# 32B48P_Dev_Board.net
KiCad netlist of a schematic drawn in Altium Designer
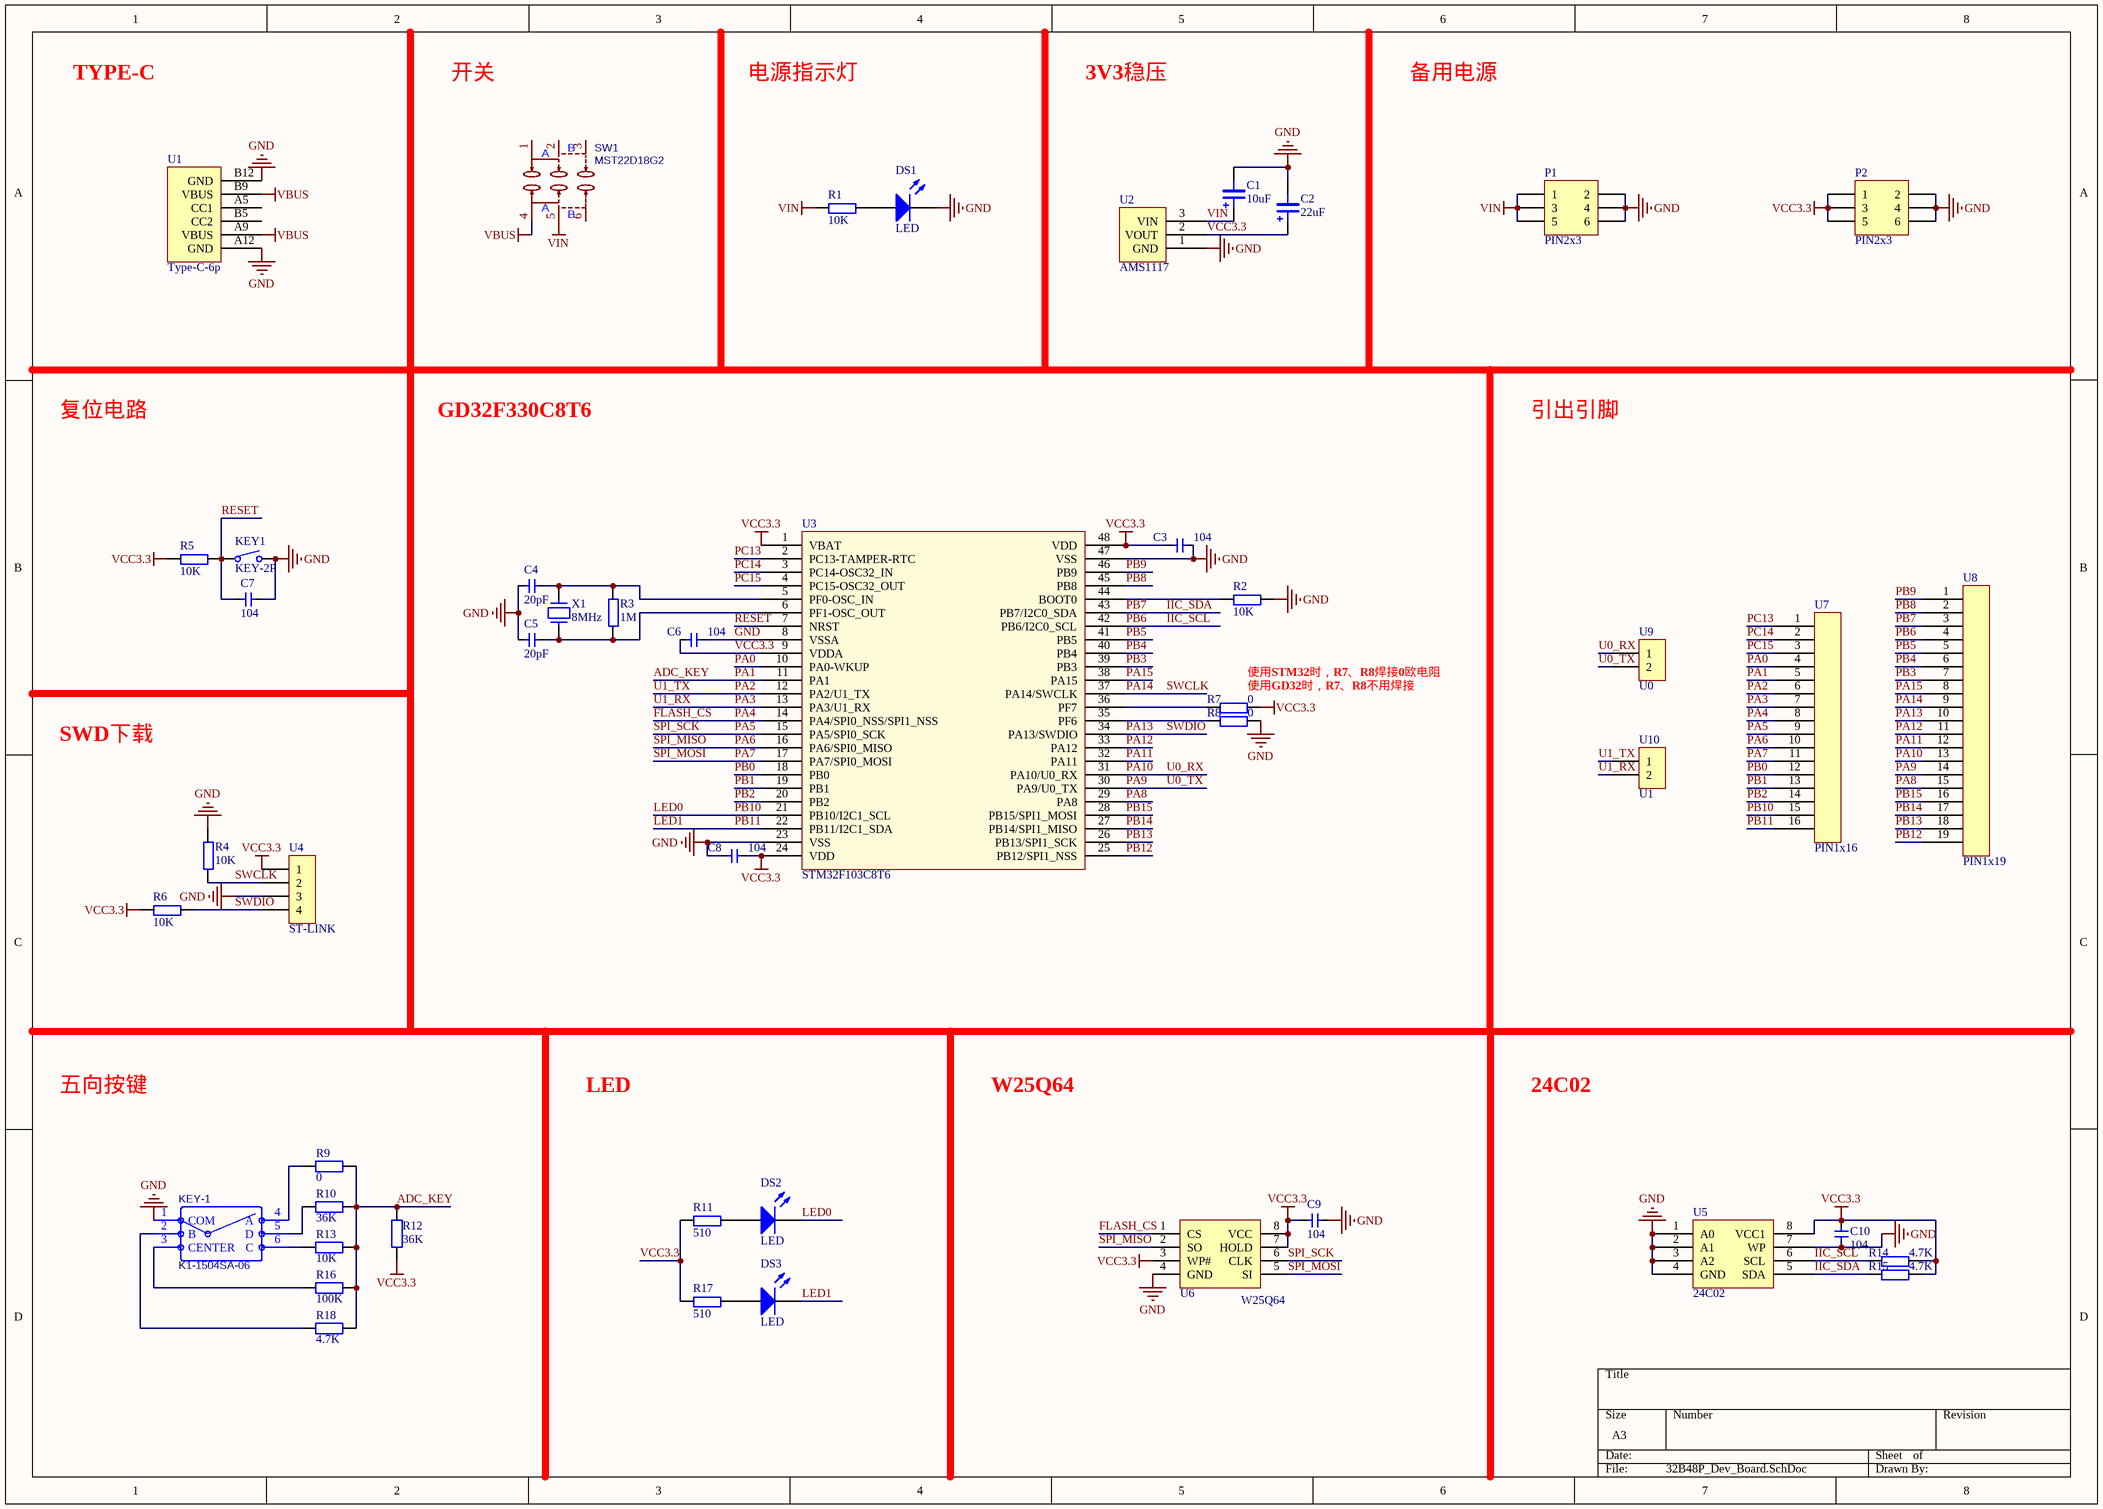
[diagram p0: 32B48P_Dev_Board.SchDoc]

(export (version "E")
  (design (tool "Eeschema 10.0.6"))
  (components
    (comp (ref "C1")
      (value "10uF")
      (footprint "CAP-TANTALUM-A")
      (description "Tantalum Capacitor")
      (libsource (lib "altium-import") (part "root_1_CAP-TANTALUM_"))
    )
    (comp (ref "C2")
      (value "22uF")
      (footprint "CAP-TANTALUM-A")
      (description "Tantalum Capacitor")
      (libsource (lib "altium-import") (part "root_1_CAP-TANTALUM_"))
    )
    (comp (ref "C3")
      (value "104")
      (footprint "Cap_0603")
      (description "Capacitor")
      (libsource (lib "altium-import") (part "root_0_CAP_"))
    )
    (comp (ref "C4")
      (value "20pF")
      (footprint "Cap_0603")
      (description "Capacitor")
      (libsource (lib "altium-import") (part "root_0_CAP_"))
    )
    (comp (ref "C5")
      (value "20pF")
      (footprint "Cap_0603")
      (description "Capacitor")
      (libsource (lib "altium-import") (part "root_0_CAP_"))
    )
    (comp (ref "C6")
      (value "104")
      (footprint "Cap_0603")
      (description "Capacitor")
      (libsource (lib "altium-import") (part "root_0_CAP_"))
    )
    (comp (ref "C7")
      (value "104")
      (footprint "Cap_0603")
      (description "Capacitor")
      (libsource (lib "altium-import") (part "root_0_CAP_"))
    )
    (comp (ref "C8")
      (value "104")
      (footprint "Cap_0603")
      (description "Capacitor")
      (libsource (lib "altium-import") (part "root_0_CAP_"))
    )
    (comp (ref "C9")
      (value "104")
      (footprint "Cap_0603")
      (description "Capacitor")
      (libsource (lib "altium-import") (part "root_0_CAP_"))
    )
    (comp (ref "C10")
      (value "104")
      (footprint "Cap_0603")
      (description "Capacitor")
      (libsource (lib "altium-import") (part "root_1_CAP_"))
    )
    (comp (ref "DS1")
      (value "LED")
      (footprint "LED_0603")
      (fields (field (name "PUBLISHER") "Altium Limited"))
      (libsource (lib "altium-import") (part "root_0_LED_"))
    )
    (comp (ref "DS2")
      (value "LED")
      (footprint "LED_0603")
      (fields (field (name "PUBLISHER") "Altium Limited"))
      (libsource (lib "altium-import") (part "root_0_LED_"))
    )
    (comp (ref "DS3")
      (value "LED")
      (footprint "LED_0603")
      (fields (field (name "PUBLISHER") "Altium Limited"))
      (libsource (lib "altium-import") (part "root_0_LED_"))
    )
    (comp (ref "KEY-1")
      (value "K1-1504SA-06")
      (footprint "SW-SMD_K1-1504SA-06")
      (description "五向按键")
      (fields (field (name "BOM_SUPPLIER PART") "C136712") (field (name "CONTRIBUTOR") "LCSC"))
      (libsource (lib "altium-import") (part "root_0_K1-1504SA-06_"))
    )
    (comp (ref "KEY1")
      (value "KEY-2P")
      (footprint "key3*6")
      (description "Switch")
      (libsource (lib "altium-import") (part "root_0_KEY-2P_"))
    )
    (comp (ref "P1")
      (value "PIN2x3")
      (footprint "PIN-2x3-2.54-1.0")
      (description "Connector")
      (libsource (lib "altium-import") (part "root_0_PIN2x3_"))
    )
    (comp (ref "P2")
      (value "PIN2x3")
      (footprint "PIN-2x3-2.54-1.0")
      (description "Connector")
      (libsource (lib "altium-import") (part "root_0_PIN2x3_"))
    )
    (comp (ref "R1")
      (value "10K")
      (footprint "Res_0603")
      (libsource (lib "altium-import") (part "root_0_RES_"))
    )
    (comp (ref "R2")
      (value "10K")
      (footprint "Res_0603")
      (libsource (lib "altium-import") (part "root_0_RES_"))
    )
    (comp (ref "R3")
      (value "1M")
      (footprint "Res_0603")
      (libsource (lib "altium-import") (part "root_1_RES_"))
    )
    (comp (ref "R4")
      (value "10K")
      (footprint "Res_0603")
      (libsource (lib "altium-import") (part "root_1_RES_"))
    )
    (comp (ref "R5")
      (value "10K")
      (footprint "Res_0603")
      (libsource (lib "altium-import") (part "root_0_RES_"))
    )
    (comp (ref "R6")
      (value "10K")
      (footprint "Res_0603")
      (libsource (lib "altium-import") (part "root_0_RES_"))
    )
    (comp (ref "R7")
      (value "0")
      (footprint "Res_0603")
      (libsource (lib "altium-import") (part "root_0_RES_"))
    )
    (comp (ref "R8")
      (value "0")
      (footprint "Res_0603")
      (libsource (lib "altium-import") (part "root_0_RES_"))
    )
    (comp (ref "R9")
      (value "0")
      (footprint "Res_0603")
      (description "Resistor")
      (libsource (lib "") (part "root_0_RES__1"))
    )
    (comp (ref "R10")
      (value "36K")
      (footprint "Res_0603")
      (description "Resistor")
      (libsource (lib "") (part "root_0_RES__1"))
    )
    (comp (ref "R11")
      (value "510")
      (footprint "Res_0603")
      (libsource (lib "altium-import") (part "root_0_RES_"))
    )
    (comp (ref "R12")
      (value "36K")
      (footprint "Res_0603")
      (description "Resistor")
      (libsource (lib "") (part "root_1_RES__1"))
    )
    (comp (ref "R13")
      (value "10K")
      (footprint "Res_0603")
      (description "Resistor")
      (libsource (lib "") (part "root_0_RES__1"))
    )
    (comp (ref "R14")
      (value "4.7K")
      (footprint "Res_0603")
      (libsource (lib "altium-import") (part "root_0_RES_"))
    )
    (comp (ref "R15")
      (value "4.7K")
      (footprint "Res_0603")
      (libsource (lib "altium-import") (part "root_0_RES_"))
    )
    (comp (ref "R16")
      (value "100K")
      (footprint "Res_0603")
      (description "Resistor")
      (libsource (lib "") (part "root_0_RES__1"))
    )
    (comp (ref "R17")
      (value "510")
      (footprint "Res_0603")
      (libsource (lib "altium-import") (part "root_0_RES_"))
    )
    (comp (ref "R18")
      (value "4.7K")
      (footprint "Res_0603")
      (description "Resistor")
      (libsource (lib "") (part "root_0_RES__1"))
    )
    (comp (ref "SW1")
      (value "MST22D18G2")
      (footprint "6脚拨动开关")
      (fields (field (name "BOM_SUPPLIER PART") "C431544") (field (name "CONTRIBUTOR") "LCSC"))
      (libsource (lib "altium-import") (part "root_0_6脚拨动开关_"))
    )
    (comp (ref "U1")
      (value "Type-C-6p")
      (footprint "TYPEC-6P")
      (libsource (lib "altium-import") (part "root_0_Type-C-6p_"))
    )
    (comp (ref "U2")
      (value "AMS1117")
      (footprint "SOT-89")
      (libsource (lib "altium-import") (part "root_2_AMS1117_"))
    )
    (comp (ref "U3")
      (value "STM32F103C8T6")
      (footprint "QFP-48-0.5")
      (libsource (lib "altium-import") (part "root_0_GD32F330Cx_"))
    )
    (comp (ref "U4")
      (value "ST-LINK")
      (footprint "st-link")
      (description "Connector")
      (libsource (lib "altium-import") (part "root_0_PIN1x4_"))
    )
    (comp (ref "U5")
      (value "24C02")
      (footprint "SOIC-8")
      (libsource (lib "altium-import") (part "root_0_24C02_"))
    )
    (comp (ref "U6")
      (value "W25Q64")
      (footprint "SOIC-8")
      (libsource (lib "altium-import") (part "root_0_W25Q64_"))
    )
    (comp (ref "U7")
      (value "PIN1x16")
      (footprint "PIN1x16")
      (libsource (lib "altium-import") (part "root_0_PIN1x16_"))
    )
    (comp (ref "U8")
      (value "PIN1x19")
      (footprint "PIN1x19")
      (libsource (lib "altium-import") (part "root_0_PIN1x19_"))
    )
    (comp (ref "U9")
      (value "U0")
      (footprint "PIN-1x2-2.54")
      (description "Connector")
      (libsource (lib "altium-import") (part "root_0_PIN1x2_"))
    )
    (comp (ref "U10")
      (value "U1")
      (footprint "PIN-1x2-2.54")
      (description "Connector")
      (libsource (lib "altium-import") (part "root_0_PIN1x2_"))
    )
    (comp (ref "X1")
      (value "8MHz")
      (footprint "OSC 5032-2P")
      (description "Crystal")
      (libsource (lib "altium-import") (part "root_0_Crystal_"))
    )
  )
  (nets
    (net (code "1") (name "/ADC_KEY") (class "Default")
      (node (ref "R10") (pin "2") (pinfunction "2_2") (pintype "passive"))
      (node (ref "R12") (pin "2") (pinfunction "2_2") (pintype "passive"))
      (node (ref "R13") (pin "2") (pinfunction "2_2") (pintype "passive"))
      (node (ref "R16") (pin "2") (pinfunction "2_2") (pintype "passive"))
      (node (ref "R18") (pin "2") (pinfunction "2_2") (pintype "passive"))
      (node (ref "R9") (pin "2") (pinfunction "2_2") (pintype "passive"))
      (node (ref "U3") (pin "11") (pinfunction "PA1_11") (pintype "passive"))
      (node (ref "U7") (pin "5") (pinfunction "5_5") (pintype "passive"))
    )
    (net (code "2") (name "/FLASH_CS") (class "Default")
      (node (ref "U3") (pin "14") (pinfunction "PA4/SPI0_NSS/SPI1_NSS_14") (pintype "passive"))
      (node (ref "U6") (pin "1") (pinfunction "CS_1") (pintype "passive"))
      (node (ref "U7") (pin "8") (pinfunction "8_8") (pintype "passive"))
    )
    (net (code "3") (name "/IIC_SCL") (class "Default")
      (node (ref "R14") (pin "1") (pintype "passive"))
      (node (ref "U3") (pin "42") (pinfunction "PB6/I2C0_SCL_42") (pintype "passive"))
      (node (ref "U5") (pin "6") (pinfunction "SCL_6") (pintype "passive"))
      (node (ref "U8") (pin "4") (pinfunction "4_4") (pintype "passive"))
    )
    (net (code "4") (name "/IIC_SDA") (class "Default")
      (node (ref "R15") (pin "1") (pintype "passive"))
      (node (ref "U3") (pin "43") (pinfunction "PB7/I2C0_SDA_43") (pintype "passive"))
      (node (ref "U5") (pin "5") (pinfunction "SDA_5") (pintype "passive"))
      (node (ref "U8") (pin "3") (pinfunction "3_3") (pintype "passive"))
    )
    (net (code "5") (name "/LED0") (class "Default")
      (node (ref "DS2") (pin "2") (pinfunction "K_2") (pintype "passive"))
      (node (ref "U3") (pin "21") (pinfunction "PB10/I2C1_SCL_21") (pintype "passive"))
      (node (ref "U7") (pin "15") (pinfunction "15_15") (pintype "passive"))
    )
    (net (code "6") (name "/LED1") (class "Default")
      (node (ref "DS3") (pin "2") (pinfunction "K_2") (pintype "passive"))
      (node (ref "U3") (pin "22") (pinfunction "PB11/I2C1_SDA_22") (pintype "passive"))
      (node (ref "U7") (pin "16") (pinfunction "16_16") (pintype "passive"))
    )
    (net (code "7") (name "/PA0") (class "Default")
      (node (ref "U3") (pin "10") (pinfunction "PA0-WKUP_10") (pintype "passive"))
      (node (ref "U7") (pin "4") (pinfunction "4_4") (pintype "passive"))
    )
    (net (code "8") (name "/PA2") (class "Default")
      (node (ref "U10") (pin "1") (pinfunction "1_1") (pintype "passive"))
      (node (ref "U3") (pin "12") (pinfunction "PA2/U1_TX_12") (pintype "passive"))
      (node (ref "U7") (pin "6") (pinfunction "6_6") (pintype "passive"))
    )
    (net (code "9") (name "/PA3") (class "Default")
      (node (ref "U10") (pin "2") (pinfunction "2_2") (pintype "passive"))
      (node (ref "U3") (pin "13") (pinfunction "PA3/U1_RX_13") (pintype "passive"))
      (node (ref "U7") (pin "7") (pinfunction "7_7") (pintype "passive"))
    )
    (net (code "10") (name "/PA5") (class "Default")
      (node (ref "U3") (pin "15") (pinfunction "PA5/SPI0_SCK_15") (pintype "passive"))
      (node (ref "U6") (pin "6") (pinfunction "CLK_6") (pintype "passive"))
      (node (ref "U7") (pin "9") (pinfunction "9_9") (pintype "passive"))
    )
    (net (code "11") (name "/PA6") (class "Default")
      (node (ref "U3") (pin "16") (pinfunction "PA6/SPI0_MISO_16") (pintype "passive"))
      (node (ref "U6") (pin "2") (pinfunction "SO_2") (pintype "passive"))
      (node (ref "U7") (pin "10") (pinfunction "10_10") (pintype "passive"))
    )
    (net (code "12") (name "/PA7") (class "Default")
      (node (ref "U3") (pin "17") (pinfunction "PA7/SPI0_MOSI_17") (pintype "passive"))
      (node (ref "U6") (pin "5") (pinfunction "SI_5") (pintype "passive"))
      (node (ref "U7") (pin "11") (pinfunction "11_11") (pintype "passive"))
    )
    (net (code "13") (name "/PA8") (class "Default")
      (node (ref "U3") (pin "29") (pinfunction "PA8_29") (pintype "passive"))
      (node (ref "U8") (pin "15") (pinfunction "15_15") (pintype "passive"))
    )
    (net (code "14") (name "/PA9") (class "Default")
      (node (ref "U3") (pin "30") (pinfunction "PA9/U0_TX_30") (pintype "passive"))
      (node (ref "U8") (pin "14") (pinfunction "14_14") (pintype "passive"))
      (node (ref "U9") (pin "2") (pinfunction "2_2") (pintype "passive"))
    )
    (net (code "15") (name "/PA10") (class "Default")
      (node (ref "U3") (pin "31") (pinfunction "PA10/U0_RX_31") (pintype "passive"))
      (node (ref "U8") (pin "13") (pinfunction "13_13") (pintype "passive"))
      (node (ref "U9") (pin "1") (pinfunction "1_1") (pintype "passive"))
    )
    (net (code "16") (name "/PA11") (class "Default")
      (node (ref "U3") (pin "32") (pinfunction "PA11_32") (pintype "passive"))
      (node (ref "U8") (pin "12") (pinfunction "12_12") (pintype "passive"))
    )
    (net (code "17") (name "/PA12") (class "Default")
      (node (ref "U3") (pin "33") (pinfunction "PA12_33") (pintype "passive"))
      (node (ref "U8") (pin "11") (pinfunction "11_11") (pintype "passive"))
    )
    (net (code "18") (name "/PA13") (class "Default")
      (node (ref "R6") (pin "2") (pintype "passive"))
      (node (ref "U3") (pin "34") (pinfunction "PA13/SWDIO_34") (pintype "passive"))
      (node (ref "U4") (pin "4") (pinfunction "4_4") (pintype "passive"))
      (node (ref "U8") (pin "10") (pinfunction "10_10") (pintype "passive"))
    )
    (net (code "19") (name "/PA14") (class "Default")
      (node (ref "R4") (pin "1") (pintype "passive"))
      (node (ref "U3") (pin "37") (pinfunction "PA14/SWCLK_37") (pintype "passive"))
      (node (ref "U4") (pin "2") (pinfunction "2_2") (pintype "passive"))
      (node (ref "U8") (pin "9") (pinfunction "9_9") (pintype "passive"))
    )
    (net (code "20") (name "/PA15") (class "Default")
      (node (ref "U3") (pin "38") (pinfunction "PA15_38") (pintype "passive"))
      (node (ref "U8") (pin "8") (pinfunction "8_8") (pintype "passive"))
    )
    (net (code "21") (name "/PB0") (class "Default")
      (node (ref "U3") (pin "18") (pinfunction "PB0_18") (pintype "passive"))
      (node (ref "U7") (pin "12") (pinfunction "12_12") (pintype "passive"))
    )
    (net (code "22") (name "/PB1") (class "Default")
      (node (ref "U3") (pin "19") (pinfunction "PB1_19") (pintype "passive"))
      (node (ref "U7") (pin "13") (pinfunction "13_13") (pintype "passive"))
    )
    (net (code "23") (name "/PB2") (class "Default")
      (node (ref "U3") (pin "20") (pinfunction "PB2_20") (pintype "passive"))
      (node (ref "U7") (pin "14") (pinfunction "14_14") (pintype "passive"))
    )
    (net (code "24") (name "/PB3") (class "Default")
      (node (ref "U3") (pin "39") (pinfunction "PB3_39") (pintype "passive"))
      (node (ref "U8") (pin "7") (pinfunction "7_7") (pintype "passive"))
    )
    (net (code "25") (name "/PB4") (class "Default")
      (node (ref "U3") (pin "40") (pinfunction "PB4_40") (pintype "passive"))
      (node (ref "U8") (pin "6") (pinfunction "6_6") (pintype "passive"))
    )
    (net (code "26") (name "/PB5") (class "Default")
      (node (ref "U3") (pin "41") (pinfunction "PB5_41") (pintype "passive"))
      (node (ref "U8") (pin "5") (pinfunction "5_5") (pintype "passive"))
    )
    (net (code "27") (name "/PB8") (class "Default")
      (node (ref "U3") (pin "45") (pinfunction "PB8_45") (pintype "passive"))
      (node (ref "U8") (pin "2") (pinfunction "2_2") (pintype "passive"))
    )
    (net (code "28") (name "/PB9") (class "Default")
      (node (ref "U3") (pin "46") (pinfunction "PB9_46") (pintype "passive"))
      (node (ref "U8") (pin "1") (pinfunction "1_1") (pintype "passive"))
    )
    (net (code "29") (name "/PB12") (class "Default")
      (node (ref "U3") (pin "25") (pinfunction "PB12/SPI1_NSS_25") (pintype "passive"))
      (node (ref "U8") (pin "19") (pinfunction "19_19") (pintype "passive"))
    )
    (net (code "30") (name "/PB13") (class "Default")
      (node (ref "U3") (pin "26") (pinfunction "PB13/SPI1_SCK_26") (pintype "passive"))
      (node (ref "U8") (pin "18") (pinfunction "18_18") (pintype "passive"))
    )
    (net (code "31") (name "/PB14") (class "Default")
      (node (ref "U3") (pin "27") (pinfunction "PB14/SPI1_MISO_27") (pintype "passive"))
      (node (ref "U8") (pin "17") (pinfunction "17_17") (pintype "passive"))
    )
    (net (code "32") (name "/PB15") (class "Default")
      (node (ref "U3") (pin "28") (pinfunction "PB15/SPI1_MOSI_28") (pintype "passive"))
      (node (ref "U8") (pin "16") (pinfunction "16_16") (pintype "passive"))
    )
    (net (code "33") (name "/PC13") (class "Default")
      (node (ref "U3") (pin "2") (pinfunction "PC13-TAMPER-RTC_2") (pintype "passive"))
      (node (ref "U7") (pin "1") (pinfunction "1_1") (pintype "passive"))
    )
    (net (code "34") (name "/PC14") (class "Default")
      (node (ref "U3") (pin "3") (pinfunction "PC14-OSC32_IN_3") (pintype "passive"))
      (node (ref "U7") (pin "2") (pinfunction "2_2") (pintype "passive"))
    )
    (net (code "35") (name "/PC15") (class "Default")
      (node (ref "U3") (pin "4") (pinfunction "PC15-OSC32_OUT_4") (pintype "passive"))
      (node (ref "U7") (pin "3") (pinfunction "3_3") (pintype "passive"))
    )
    (net (code "36") (name "/RESET") (class "Default")
      (node (ref "C7") (pin "1") (pinfunction "1_1") (pintype "passive"))
      (node (ref "KEY1") (pin "1") (pinfunction "1_1") (pintype "passive"))
      (node (ref "R5") (pin "2") (pintype "passive"))
      (node (ref "U3") (pin "7") (pinfunction "NRST_7") (pintype "passive"))
    )
    (net (code "37") (name "GND") (class "Default")
      (node (ref "C1") (pin "2") (pinfunction "2_2") (pintype "passive"))
      (node (ref "C10") (pin "1") (pinfunction "1_1") (pintype "passive"))
      (node (ref "C2") (pin "2") (pinfunction "2_2") (pintype "passive"))
      (node (ref "C3") (pin "2") (pinfunction "2_2") (pintype "passive"))
      (node (ref "C4") (pin "1") (pinfunction "1_1") (pintype "passive"))
      (node (ref "C5") (pin "1") (pinfunction "1_1") (pintype "passive"))
      (node (ref "C6") (pin "2") (pinfunction "2_2") (pintype "passive"))
      (node (ref "C7") (pin "2") (pinfunction "2_2") (pintype "passive"))
      (node (ref "C8") (pin "1") (pinfunction "1_1") (pintype "passive"))
      (node (ref "C9") (pin "2") (pinfunction "2_2") (pintype "passive"))
      (node (ref "DS1") (pin "2") (pinfunction "K_2") (pintype "passive"))
      (node (ref "KEY-1") (pin "1") (pinfunction "COM_1") (pintype "passive"))
      (node (ref "KEY1") (pin "2") (pinfunction "2_2") (pintype "passive"))
      (node (ref "P1") (pin "2") (pinfunction "2_2") (pintype "passive"))
      (node (ref "P1") (pin "4") (pinfunction "4_4") (pintype "passive"))
      (node (ref "P1") (pin "6") (pinfunction "6_6") (pintype "passive"))
      (node (ref "P2") (pin "2") (pinfunction "2_2") (pintype "passive"))
      (node (ref "P2") (pin "4") (pinfunction "4_4") (pintype "passive"))
      (node (ref "P2") (pin "6") (pinfunction "6_6") (pintype "passive"))
      (node (ref "R2") (pin "2") (pintype "passive"))
      (node (ref "R4") (pin "2") (pintype "passive"))
      (node (ref "R8") (pin "2") (pintype "passive"))
      (node (ref "U1") (pin "A12") (pinfunction "GND_A12") (pintype "passive"))
      (node (ref "U1") (pin "B12") (pinfunction "GND_B12") (pintype "passive"))
      (node (ref "U2") (pin "1") (pinfunction "GND_1") (pintype "passive"))
      (node (ref "U3") (pin "23") (pinfunction "VSS_23") (pintype "passive"))
      (node (ref "U3") (pin "47") (pinfunction "VSS_47") (pintype "passive"))
      (node (ref "U3") (pin "8") (pinfunction "VSSA_8") (pintype "passive"))
      (node (ref "U4") (pin "3") (pinfunction "3_3") (pintype "passive"))
      (node (ref "U5") (pin "1") (pinfunction "A0_1") (pintype "passive"))
      (node (ref "U5") (pin "2") (pinfunction "A1_2") (pintype "passive"))
      (node (ref "U5") (pin "3") (pinfunction "A2_3") (pintype "passive"))
      (node (ref "U5") (pin "4") (pinfunction "GND_4") (pintype "passive"))
      (node (ref "U5") (pin "7") (pinfunction "WP_7") (pintype "passive"))
      (node (ref "U6") (pin "4") (pinfunction "GND_4") (pintype "passive"))
    )
    (net (code "38") (name "Net-(DS1-A)") (class "Default")
      (node (ref "DS1") (pin "1") (pinfunction "A_1") (pintype "passive"))
      (node (ref "R1") (pin "2") (pintype "passive"))
    )
    (net (code "39") (name "Net-(DS2-A)") (class "Default")
      (node (ref "DS2") (pin "1") (pinfunction "A_1") (pintype "passive"))
      (node (ref "R11") (pin "2") (pintype "passive"))
    )
    (net (code "40") (name "Net-(DS3-A)") (class "Default")
      (node (ref "DS3") (pin "1") (pinfunction "A_1") (pintype "passive"))
      (node (ref "R17") (pin "2") (pintype "passive"))
    )
    (net (code "41") (name "Net-(KEY-1-A)") (class "Default")
      (node (ref "KEY-1") (pin "4") (pinfunction "A_4") (pintype "passive"))
      (node (ref "R9") (pin "1") (pinfunction "1_1") (pintype "passive"))
    )
    (net (code "42") (name "Net-(KEY-1-B)") (class "Default")
      (node (ref "KEY-1") (pin "2") (pinfunction "B_2") (pintype "passive"))
      (node (ref "R18") (pin "1") (pinfunction "1_1") (pintype "passive"))
    )
    (net (code "43") (name "Net-(KEY-1-C)") (class "Default")
      (node (ref "KEY-1") (pin "6") (pinfunction "C_6") (pintype "passive"))
      (node (ref "R13") (pin "1") (pinfunction "1_1") (pintype "passive"))
    )
    (net (code "44") (name "Net-(KEY-1-CENTER)") (class "Default")
      (node (ref "KEY-1") (pin "3") (pinfunction "CENTER_3") (pintype "passive"))
      (node (ref "R16") (pin "1") (pinfunction "1_1") (pintype "passive"))
    )
    (net (code "45") (name "Net-(KEY-1-D)") (class "Default")
      (node (ref "KEY-1") (pin "5") (pinfunction "D_5") (pintype "passive"))
      (node (ref "R10") (pin "1") (pinfunction "1_1") (pintype "passive"))
    )
    (net (code "46") (name "Net-(U3-BOOT0)") (class "Default")
      (node (ref "R2") (pin "1") (pintype "passive"))
      (node (ref "U3") (pin "44") (pinfunction "BOOT0_44") (pintype "passive"))
    )
    (net (code "47") (name "Net-(U3-PF0-OSC_IN)") (class "Default")
      (node (ref "C4") (pin "2") (pinfunction "2_2") (pintype "passive"))
      (node (ref "R3") (pin "2") (pintype "passive"))
      (node (ref "U3") (pin "5") (pinfunction "PF0-OSC_IN_5") (pintype "passive"))
      (node (ref "X1") (pin "1") (pinfunction "1_1") (pintype "passive"))
    )
    (net (code "48") (name "Net-(U3-PF1-OSC_OUT)") (class "Default")
      (node (ref "C5") (pin "2") (pinfunction "2_2") (pintype "passive"))
      (node (ref "R3") (pin "1") (pintype "passive"))
      (node (ref "U3") (pin "6") (pinfunction "PF1-OSC_OUT_6") (pintype "passive"))
      (node (ref "X1") (pin "2") (pinfunction "2_2") (pintype "passive"))
    )
    (net (code "49") (name "Net-(U3-PF6)") (class "Default")
      (node (ref "R8") (pin "1") (pintype "passive"))
      (node (ref "U3") (pin "35") (pinfunction "PF6_35") (pintype "passive"))
    )
    (net (code "50") (name "Net-(U3-PF7)") (class "Default")
      (node (ref "R7") (pin "1") (pintype "passive"))
      (node (ref "U3") (pin "36") (pinfunction "PF7_36") (pintype "passive"))
    )
    (net (code "51") (name "VBUS") (class "Default")
      (node (ref "SW1") (pin "4") (pinfunction "4_4") (pintype "passive"))
      (node (ref "U1") (pin "A9") (pinfunction "VBUS_A9") (pintype "passive"))
      (node (ref "U1") (pin "B9") (pinfunction "VBUS_B9") (pintype "passive"))
    )
    (net (code "52") (name "VCC3.3") (class "Default")
      (node (ref "C10") (pin "2") (pinfunction "2_2") (pintype "passive"))
      (node (ref "C2") (pin "1") (pinfunction "1_1") (pintype "passive"))
      (node (ref "C3") (pin "1") (pinfunction "1_1") (pintype "passive"))
      (node (ref "C6") (pin "1") (pinfunction "1_1") (pintype "passive"))
      (node (ref "C8") (pin "2") (pinfunction "2_2") (pintype "passive"))
      (node (ref "C9") (pin "1") (pinfunction "1_1") (pintype "passive"))
      (node (ref "P2") (pin "1") (pinfunction "1_1") (pintype "passive"))
      (node (ref "P2") (pin "3") (pinfunction "3_3") (pintype "passive"))
      (node (ref "P2") (pin "5") (pinfunction "5_5") (pintype "passive"))
      (node (ref "R11") (pin "1") (pintype "passive"))
      (node (ref "R12") (pin "1") (pinfunction "1_1") (pintype "passive"))
      (node (ref "R14") (pin "2") (pintype "passive"))
      (node (ref "R15") (pin "2") (pintype "passive"))
      (node (ref "R17") (pin "1") (pintype "passive"))
      (node (ref "R5") (pin "1") (pintype "passive"))
      (node (ref "R6") (pin "1") (pintype "passive"))
      (node (ref "R7") (pin "2") (pintype "passive"))
      (node (ref "U2") (pin "2") (pinfunction "VOUT_2") (pintype "passive"))
      (node (ref "U3") (pin "1") (pinfunction "VBAT_1") (pintype "passive"))
      (node (ref "U3") (pin "24") (pinfunction "VDD_24") (pintype "passive"))
      (node (ref "U3") (pin "48") (pinfunction "VDD_48") (pintype "passive"))
      (node (ref "U3") (pin "9") (pinfunction "VDDA_9") (pintype "passive"))
      (node (ref "U4") (pin "1") (pinfunction "1_1") (pintype "passive"))
      (node (ref "U5") (pin "8") (pinfunction "VCC1_8") (pintype "passive"))
      (node (ref "U6") (pin "3") (pinfunction "WP#_3") (pintype "passive"))
      (node (ref "U6") (pin "7") (pinfunction "HOLD_7") (pintype "passive"))
      (node (ref "U6") (pin "8") (pinfunction "VCC_8") (pintype "passive"))
    )
    (net (code "53") (name "VIN") (class "Default")
      (node (ref "C1") (pin "1") (pinfunction "1_1") (pintype "passive"))
      (node (ref "P1") (pin "1") (pinfunction "1_1") (pintype "passive"))
      (node (ref "P1") (pin "3") (pinfunction "3_3") (pintype "passive"))
      (node (ref "P1") (pin "5") (pinfunction "5_5") (pintype "passive"))
      (node (ref "R1") (pin "1") (pintype "passive"))
      (node (ref "SW1") (pin "5") (pinfunction "5_5") (pintype "passive"))
      (node (ref "U2") (pin "3") (pinfunction "VIN_3") (pintype "passive"))
    )
    (net (code "54") (name "unconnected-(SW1-Pad1)") (class "Default")
      (node (ref "SW1") (pin "1") (pinfunction "1_1") (pintype "passive"))
    )
    (net (code "55") (name "unconnected-(SW1-Pad2)") (class "Default")
      (node (ref "SW1") (pin "2") (pinfunction "2_2") (pintype "passive"))
    )
    (net (code "56") (name "unconnected-(SW1-Pad3)") (class "Default")
      (node (ref "SW1") (pin "3") (pinfunction "3_3") (pintype "passive"))
    )
    (net (code "57") (name "unconnected-(SW1-Pad6)") (class "Default")
      (node (ref "SW1") (pin "6") (pinfunction "6_6") (pintype "passive"))
    )
    (net (code "58") (name "unconnected-(U1-CC1-PadA5)") (class "Default")
      (node (ref "U1") (pin "A5") (pinfunction "CC1_A5") (pintype "passive"))
    )
    (net (code "59") (name "unconnected-(U1-CC2-PadB5)") (class "Default")
      (node (ref "U1") (pin "B5") (pinfunction "CC2_B5") (pintype "passive"))
    )
  )
)
